# JDY-40_Rx.net
KiCad netlist of a schematic drawn in EAGLE
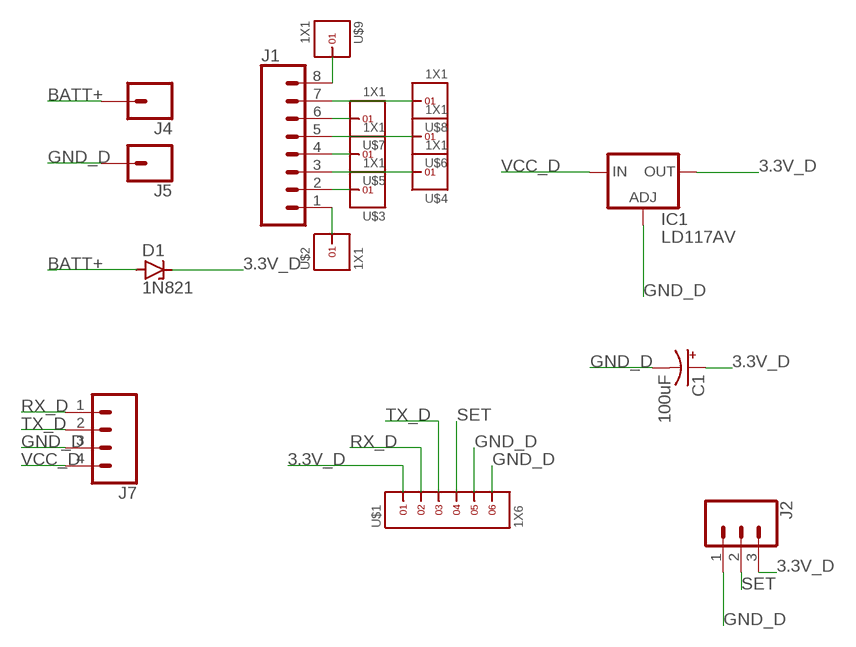
[diagram p0: schematic, sheet 1]

(export (version "E")
  (design (tool "Eeschema 10.0.6"))
  (components
    (comp (ref "C1")
      (value "100uF")
      (footprint "eagle-import:CPOL-RADIAL-2.5MM-6.5MM")
      (libsource (lib "eagle-import") (part "100UF-POLAR-RADIAL-2.5MM-25V-20%"))
    )
    (comp (ref "D1")
      (value "1N821")
      (footprint "eagle-import:DO35Z10")
      (libsource (lib "eagle-import") (part "1N821"))
    )
    (comp (ref "IC1")
      (value "LD117AV")
      (footprint "eagle-import:TO220L1")
      (libsource (lib "eagle-import") (part "LD117A?V"))
    )
    (comp (ref "J1")
      (value "CONN_08\"")
      (footprint "eagle-import:1X08")
      (libsource (lib "eagle-import") (part "CONN_08{dblquote}"))
    )
    (comp (ref "J2")
      (value "CONN_03")
      (footprint "eagle-import:1X03")
      (libsource (lib "eagle-import") (part "CONN_03"))
    )
    (comp (ref "J4")
      (value "CONN_01")
      (footprint "eagle-import:1X01")
      (libsource (lib "eagle-import") (part "CONN_01"))
    )
    (comp (ref "J5")
      (value "CONN_01")
      (footprint "eagle-import:1X01")
      (libsource (lib "eagle-import") (part "CONN_01"))
    )
    (comp (ref "J7")
      (value "CONN_04")
      (footprint "eagle-import:1X04")
      (libsource (lib "eagle-import") (part "CONN_04"))
    )
    (comp (ref "U$1")
      (value "1X6")
      (footprint "eagle-import:1X6")
      (libsource (lib "eagle-import") (part "1X6"))
    )
    (comp (ref "U$2")
      (value "1X1")
      (footprint "eagle-import:1X1")
      (libsource (lib "eagle-import") (part "1X1"))
    )
    (comp (ref "U$3")
      (value "1X1")
      (footprint "eagle-import:1X1")
      (libsource (lib "eagle-import") (part "1X1"))
    )
    (comp (ref "U$4")
      (value "1X1")
      (footprint "eagle-import:1X1")
      (libsource (lib "eagle-import") (part "1X1"))
    )
    (comp (ref "U$5")
      (value "1X1")
      (footprint "eagle-import:1X1")
      (libsource (lib "eagle-import") (part "1X1"))
    )
    (comp (ref "U$6")
      (value "1X1")
      (footprint "eagle-import:1X1")
      (libsource (lib "eagle-import") (part "1X1"))
    )
    (comp (ref "U$7")
      (value "1X1")
      (footprint "eagle-import:1X1")
      (libsource (lib "eagle-import") (part "1X1"))
    )
    (comp (ref "U$8")
      (value "1X1")
      (footprint "eagle-import:1X1")
      (libsource (lib "eagle-import") (part "1X1"))
    )
    (comp (ref "U$9")
      (value "1X1")
      (footprint "eagle-import:1X1")
      (libsource (lib "eagle-import") (part "1X1"))
    )
  )
  (nets
    (net (code "1") (name "/3.3V_D") (class "Default")
      (node (ref "C1") (pin "1") (pinfunction "+_1") (pintype "passive"))
      (node (ref "D1") (pin "C") (pinfunction "C_C") (pintype "passive"))
      (node (ref "IC1") (pin "2") (pinfunction "OUT_2") (pintype "passive"))
      (node (ref "J2") (pin "3") (pinfunction "3_3") (pintype "passive"))
      (node (ref "U$1") (pin "1") (pinfunction "1_1") (pintype "bidirectional"))
    )
    (net (code "2") (name "/BATT+") (class "Default")
      (node (ref "D1") (pin "A") (pinfunction "A_A") (pintype "passive"))
      (node (ref "J4") (pin "1") (pinfunction "1_1") (pintype "passive"))
    )
    (net (code "3") (name "/GND_D") (class "Default")
      (node (ref "C1") (pin "2") (pinfunction "-_2") (pintype "passive"))
      (node (ref "IC1") (pin "1") (pinfunction "ADJ_1") (pintype "input"))
      (node (ref "J2") (pin "1") (pinfunction "1_1") (pintype "passive"))
      (node (ref "J5") (pin "1") (pinfunction "1_1") (pintype "passive"))
      (node (ref "J7") (pin "3") (pinfunction "3_3") (pintype "passive"))
      (node (ref "U$1") (pin "5") (pinfunction "5_5") (pintype "bidirectional"))
      (node (ref "U$1") (pin "6") (pinfunction "6_6") (pintype "bidirectional"))
    )
    (net (code "4") (name "/RX_D") (class "Default")
      (node (ref "J7") (pin "1") (pinfunction "1_1") (pintype "passive"))
      (node (ref "U$1") (pin "2") (pinfunction "2_2") (pintype "bidirectional"))
    )
    (net (code "5") (name "/SET") (class "Default")
      (node (ref "J2") (pin "2") (pinfunction "2_2") (pintype "passive"))
      (node (ref "U$1") (pin "4") (pinfunction "4_4") (pintype "bidirectional"))
    )
    (net (code "6") (name "/TX_D") (class "Default")
      (node (ref "J7") (pin "2") (pinfunction "2_2") (pintype "passive"))
      (node (ref "U$1") (pin "3") (pinfunction "3_3") (pintype "bidirectional"))
    )
    (net (code "7") (name "/VCC_D") (class "Default")
      (node (ref "IC1") (pin "3") (pinfunction "IN_3") (pintype "input"))
      (node (ref "J7") (pin "4") (pinfunction "4_4") (pintype "passive"))
    )
    (net (code "8") (name "Net-(J1-Pad1)") (class "Default")
      (node (ref "J1") (pin "1") (pinfunction "1_1") (pintype "passive"))
      (node (ref "U$2") (pin "1") (pinfunction "1_1") (pintype "bidirectional"))
    )
    (net (code "9") (name "Net-(J1-Pad2)") (class "Default")
      (node (ref "J1") (pin "2") (pinfunction "2_2") (pintype "passive"))
      (node (ref "U$3") (pin "1") (pinfunction "1_1") (pintype "bidirectional"))
    )
    (net (code "10") (name "Net-(J1-Pad3)") (class "Default")
      (node (ref "J1") (pin "3") (pinfunction "3_3") (pintype "passive"))
      (node (ref "U$4") (pin "1") (pinfunction "1_1") (pintype "bidirectional"))
    )
    (net (code "11") (name "Net-(J1-Pad4)") (class "Default")
      (node (ref "J1") (pin "4") (pinfunction "4_4") (pintype "passive"))
      (node (ref "U$5") (pin "1") (pinfunction "1_1") (pintype "bidirectional"))
    )
    (net (code "12") (name "Net-(J1-Pad5)") (class "Default")
      (node (ref "J1") (pin "5") (pinfunction "5_5") (pintype "passive"))
      (node (ref "U$6") (pin "1") (pinfunction "1_1") (pintype "bidirectional"))
    )
    (net (code "13") (name "Net-(J1-Pad6)") (class "Default")
      (node (ref "J1") (pin "6") (pinfunction "6_6") (pintype "passive"))
      (node (ref "U$7") (pin "1") (pinfunction "1_1") (pintype "bidirectional"))
    )
    (net (code "14") (name "Net-(J1-Pad7)") (class "Default")
      (node (ref "J1") (pin "7") (pinfunction "7_7") (pintype "passive"))
      (node (ref "U$8") (pin "1") (pinfunction "1_1") (pintype "bidirectional"))
    )
    (net (code "15") (name "Net-(J1-Pad8)") (class "Default")
      (node (ref "J1") (pin "8") (pinfunction "8_8") (pintype "passive"))
      (node (ref "U$9") (pin "1") (pinfunction "1_1") (pintype "bidirectional"))
    )
  )
)
